# Diff.net
KiCad netlist of a schematic drawn in Altium Designer
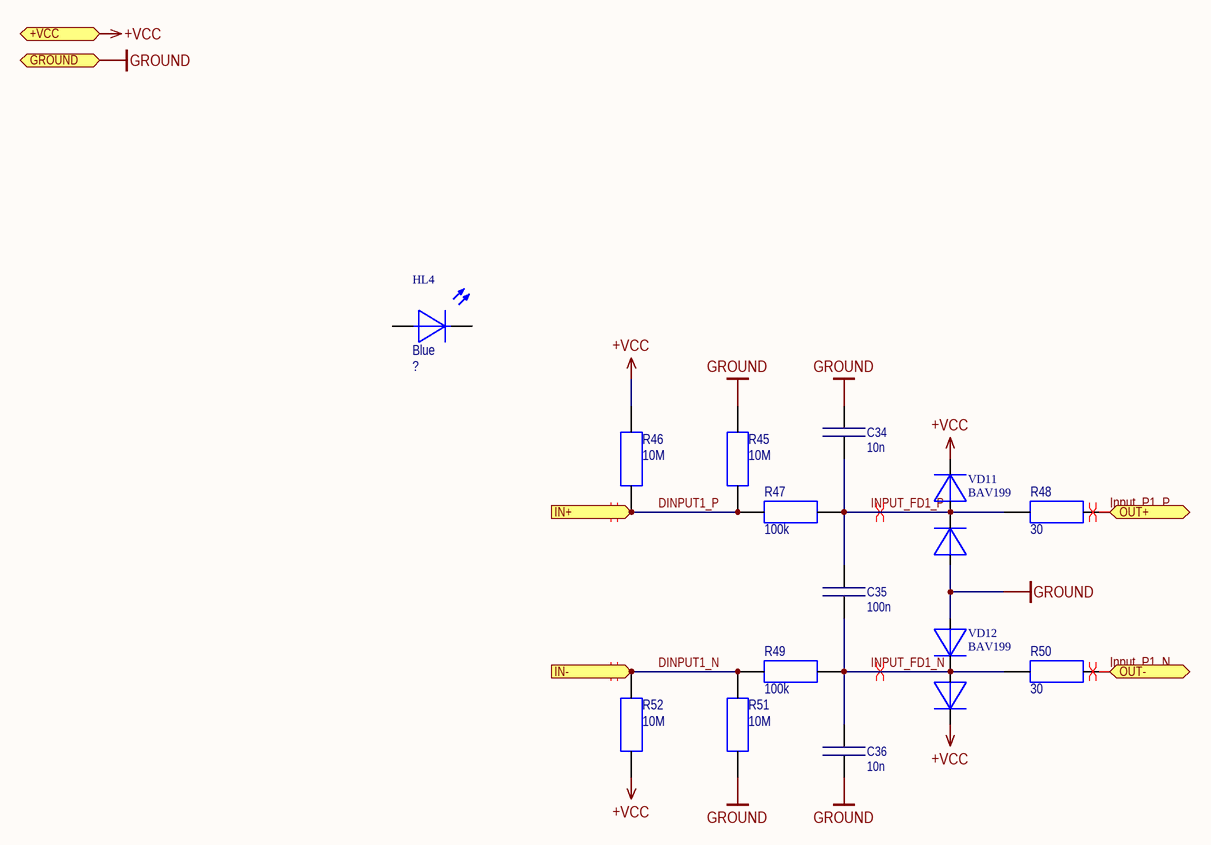
[diagram p0: Diff.SchDoc]

(export (version "E")
  (design (tool "Eeschema 10.0.6"))
  (components
    (comp (ref "C34")
      (value "10n")
      (footprint "SMDRC0805")
      (description "Generic capasitor non-polar")
      (fields (field (name "PARTNUMBER") "Capacitor 0805 10n"))
      (libsource (lib "library") (part "Capacitor"))
    )
    (comp (ref "C35")
      (value "100n")
      (footprint "SMDRC0805")
      (description "Generic capasitor non-polar")
      (fields (field (name "PARTNUMBER") "Capacitor 0805 100n"))
      (libsource (lib "library") (part "Capacitor"))
    )
    (comp (ref "C36")
      (value "10n")
      (footprint "SMDRC0805")
      (description "Generic capasitor non-polar")
      (fields (field (name "PARTNUMBER") "Capacitor 0805 10n"))
      (libsource (lib "library") (part "Capacitor"))
    )
    (comp (ref "HL4")
      (value "Blue")
      (footprint "Indicator:DIOMELF2012M")
      (description "Diod LED SMD Blue")
      (fields (field (name "MANUFACTURERPARTNUMBER") "?"))
      (libsource (lib "Indicator") (part "LED1_B"))
    )
    (comp (ref "R45")
      (value "10M")
      (footprint "SMDRC0805")
      (description "Generic resistor")
      (fields (field (name "PARTNUMBER") "Resistor 0805 10M"))
      (libsource (lib "") (part "Resistor_1"))
    )
    (comp (ref "R46")
      (value "10M")
      (footprint "SMDRC0805")
      (description "Generic resistor")
      (fields (field (name "PARTNUMBER") "Resistor 0805 10M"))
      (libsource (lib "") (part "Resistor_1"))
    )
    (comp (ref "R47")
      (value "100k")
      (footprint "SMDRC0805")
      (description "Generic resistor")
      (fields (field (name "PARTNUMBER") "Resistor 0805 100k"))
      (libsource (lib "") (part "Resistor_1"))
    )
    (comp (ref "R48")
      (value "30")
      (footprint "SMDRC0805")
      (description "Generic resistor")
      (fields (field (name "PARTNUMBER") "Resistor 0805 30"))
      (libsource (lib "library") (part "Resistor"))
    )
    (comp (ref "R49")
      (value "100k")
      (footprint "SMDRC0805")
      (description "Generic resistor")
      (fields (field (name "PARTNUMBER") "Resistor 0805 100k"))
      (libsource (lib "") (part "Resistor_1"))
    )
    (comp (ref "R50")
      (value "30")
      (footprint "SMDRC0805")
      (description "Generic resistor")
      (fields (field (name "PARTNUMBER") "Resistor 0805 30"))
      (libsource (lib "library") (part "Resistor"))
    )
    (comp (ref "R51")
      (value "10M")
      (footprint "SMDRC0805")
      (description "Generic resistor")
      (fields (field (name "PARTNUMBER") "Resistor 0805 10M"))
      (libsource (lib "") (part "Resistor_1"))
    )
    (comp (ref "R52")
      (value "10M")
      (footprint "SMDRC0805")
      (description "Generic resistor")
      (fields (field (name "PARTNUMBER") "Resistor 0805 10M"))
      (libsource (lib "") (part "Resistor_1"))
    )
    (comp (ref "VD11")
      (value "BAV199")
      (footprint "Standard:SOT23 (TO-236AB)")
      (fields (field (name "MANUFACTURER") "NXP"))
      (libsource (lib "Diod") (part "BAV199"))
    )
    (comp (ref "VD12")
      (value "BAV199")
      (footprint "Standard:SOT23 (TO-236AB)")
      (fields (field (name "MANUFACTURER") "NXP"))
      (libsource (lib "Diod") (part "BAV199"))
    )
  )
  (nets
    (net (code "1") (name "+VCC") (class "Default")
      (node (ref "R46") (pin "2") (pinfunction "2_2") (pintype "passive"))
      (node (ref "R52") (pin "1") (pinfunction "1_1") (pintype "passive"))
      (node (ref "VD11") (pin "2") (pinfunction "2_2") (pintype "passive"))
      (node (ref "VD12") (pin "2") (pinfunction "2_2") (pintype "passive"))
    )
    (net (code "2") (name "/DINPUT1_N") (class "Default")
      (node (ref "R49") (pin "1") (pinfunction "1_1") (pintype "passive"))
      (node (ref "R51") (pin "2") (pinfunction "2_2") (pintype "passive"))
      (node (ref "R52") (pin "2") (pinfunction "2_2") (pintype "passive"))
    )
    (net (code "3") (name "/DINPUT1_P") (class "Default")
      (node (ref "R45") (pin "1") (pinfunction "1_1") (pintype "passive"))
      (node (ref "R46") (pin "1") (pinfunction "1_1") (pintype "passive"))
      (node (ref "R47") (pin "1") (pinfunction "1_1") (pintype "passive"))
    )
    (net (code "4") (name "/INPUT_FD1_N") (class "Default")
      (node (ref "C35") (pin "1") (pintype "passive"))
      (node (ref "C36") (pin "2") (pintype "passive"))
      (node (ref "R49") (pin "2") (pinfunction "2_2") (pintype "passive"))
      (node (ref "R50") (pin "1") (pinfunction "1_1") (pintype "passive"))
      (node (ref "VD12") (pin "3") (pinfunction "3_3") (pintype "passive"))
    )
    (net (code "5") (name "/INPUT_FD1_P") (class "Default")
      (node (ref "C34") (pin "1") (pintype "passive"))
      (node (ref "C35") (pin "2") (pintype "passive"))
      (node (ref "R47") (pin "2") (pinfunction "2_2") (pintype "passive"))
      (node (ref "R48") (pin "1") (pinfunction "1_1") (pintype "passive"))
      (node (ref "VD11") (pin "3") (pinfunction "3_3") (pintype "passive"))
    )
    (net (code "6") (name "/Input_P1_N") (class "Default")
      (node (ref "R50") (pin "2") (pinfunction "2_2") (pintype "passive"))
    )
    (net (code "7") (name "/Input_P1_P") (class "Default")
      (node (ref "R48") (pin "2") (pinfunction "2_2") (pintype "passive"))
    )
    (net (code "10") (name "GROUND") (class "Default")
      (node (ref "C34") (pin "2") (pintype "passive"))
      (node (ref "C36") (pin "1") (pintype "passive"))
      (node (ref "R45") (pin "2") (pinfunction "2_2") (pintype "passive"))
      (node (ref "R51") (pin "1") (pinfunction "1_1") (pintype "passive"))
      (node (ref "VD11") (pin "1") (pinfunction "1_1") (pintype "passive"))
      (node (ref "VD12") (pin "1") (pinfunction "1_1") (pintype "passive"))
    )
    (net (code "11") (name "unconnected-(HL4-Pad1)") (class "Default")
      (node (ref "HL4") (pin "1") (pinfunction "1_1") (pintype "passive"))
    )
    (net (code "12") (name "unconnected-(HL4-Pad2)") (class "Default")
      (node (ref "HL4") (pin "2") (pinfunction "2_2") (pintype "passive"))
    )
  )
)
